# untitled.net
KiCad netlist of a schematic drawn in EAGLE
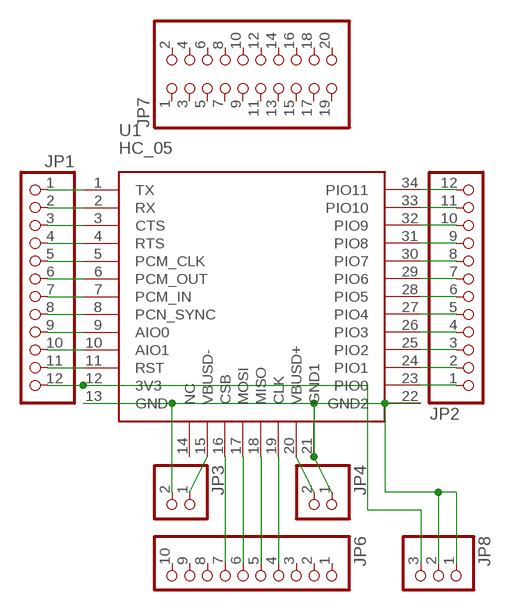
[diagram p0: schematic, sheet 1]

(export (version "E")
  (design (tool "Eeschema 10.0.6"))
  (components
    (comp (ref "JP1")
      (value "PINHD-1X12")
      (footprint "eagle-import:1X12")
      (libsource (lib "eagle-import") (part "PINHD-1X12"))
    )
    (comp (ref "JP2")
      (value "PINHD-1X12")
      (footprint "eagle-import:1X12")
      (libsource (lib "eagle-import") (part "PINHD-1X12"))
    )
    (comp (ref "JP3")
      (value "PINHD-1X2")
      (footprint "eagle-import:1X02")
      (libsource (lib "eagle-import") (part "PINHD-1X2"))
    )
    (comp (ref "JP4")
      (value "PINHD-1X2")
      (footprint "eagle-import:1X02")
      (libsource (lib "eagle-import") (part "PINHD-1X2"))
    )
    (comp (ref "JP6")
      (value "PINHD-1X10")
      (footprint "eagle-import:1X10")
      (libsource (lib "eagle-import") (part "PINHD-1X10"))
    )
    (comp (ref "JP7")
      (value "PINHD-2X10")
      (footprint "eagle-import:2X10")
      (libsource (lib "eagle-import") (part "PINHD-2X10"))
    )
    (comp (ref "JP8")
      (value "PINHD-1X3")
      (footprint "eagle-import:1X03")
      (libsource (lib "eagle-import") (part "PINHD-1X3"))
    )
    (comp (ref "U1")
      (value "HC_05")
      (footprint "eagle-import:BLUETOOTH_SMD")
      (libsource (lib "eagle-import") (part "HC_05"))
    )
  )
  (nets
    (net (code "1") (name "Net-(U1-3V3)") (class "Default")
      (node (ref "JP1") (pin "12") (pinfunction "12_12") (pintype "passive"))
      (node (ref "JP8") (pin "3") (pinfunction "3_3") (pintype "passive"))
      (node (ref "U1") (pin "12") (pinfunction "3V3_12") (pintype "bidirectional"))
    )
    (net (code "2") (name "Net-(U1-AIO0)") (class "Default")
      (node (ref "JP1") (pin "9") (pinfunction "9_9") (pintype "passive"))
      (node (ref "U1") (pin "9") (pinfunction "AIO0_9") (pintype "bidirectional"))
    )
    (net (code "3") (name "Net-(U1-AIO1)") (class "Default")
      (node (ref "JP1") (pin "10") (pinfunction "10_10") (pintype "passive"))
      (node (ref "U1") (pin "10") (pinfunction "AIO1_10") (pintype "bidirectional"))
    )
    (net (code "4") (name "Net-(U1-CLK)") (class "Default")
      (node (ref "JP6") (pin "4") (pinfunction "4_4") (pintype "passive"))
      (node (ref "U1") (pin "19") (pinfunction "CLK_19") (pintype "bidirectional"))
    )
    (net (code "5") (name "Net-(U1-CSB)") (class "Default")
      (node (ref "JP6") (pin "7") (pinfunction "7_7") (pintype "passive"))
      (node (ref "U1") (pin "16") (pinfunction "CSB_16") (pintype "bidirectional"))
    )
    (net (code "6") (name "Net-(U1-CTS)") (class "Default")
      (node (ref "JP1") (pin "3") (pinfunction "3_3") (pintype "passive"))
      (node (ref "U1") (pin "3") (pinfunction "CTS_3") (pintype "bidirectional"))
    )
    (net (code "7") (name "Net-(U1-GND)") (class "Default")
      (node (ref "JP3") (pin "2") (pinfunction "2_2") (pintype "passive"))
      (node (ref "JP4") (pin "1") (pinfunction "1_1") (pintype "passive"))
      (node (ref "JP8") (pin "1") (pinfunction "1_1") (pintype "passive"))
      (node (ref "JP8") (pin "2") (pinfunction "2_2") (pintype "passive"))
      (node (ref "U1") (pin "13") (pinfunction "GND_13") (pintype "bidirectional"))
      (node (ref "U1") (pin "21") (pinfunction "GND1_21") (pintype "bidirectional"))
      (node (ref "U1") (pin "22") (pinfunction "GND2_22") (pintype "bidirectional"))
    )
    (net (code "8") (name "Net-(U1-MISO)") (class "Default")
      (node (ref "JP6") (pin "5") (pinfunction "5_5") (pintype "passive"))
      (node (ref "U1") (pin "18") (pinfunction "MISO_18") (pintype "bidirectional"))
    )
    (net (code "9") (name "Net-(U1-MOSI)") (class "Default")
      (node (ref "JP6") (pin "6") (pinfunction "6_6") (pintype "passive"))
      (node (ref "U1") (pin "17") (pinfunction "MOSI_17") (pintype "bidirectional"))
    )
    (net (code "10") (name "Net-(U1-PCM_CLK)") (class "Default")
      (node (ref "JP1") (pin "5") (pinfunction "5_5") (pintype "passive"))
      (node (ref "U1") (pin "5") (pinfunction "PCM_CLK_5") (pintype "bidirectional"))
    )
    (net (code "11") (name "Net-(U1-PCM_IN)") (class "Default")
      (node (ref "JP1") (pin "7") (pinfunction "7_7") (pintype "passive"))
      (node (ref "U1") (pin "7") (pinfunction "PCM_IN_7") (pintype "bidirectional"))
    )
    (net (code "12") (name "Net-(U1-PCM_OUT)") (class "Default")
      (node (ref "JP1") (pin "6") (pinfunction "6_6") (pintype "passive"))
      (node (ref "U1") (pin "6") (pinfunction "PCM_OUT_6") (pintype "bidirectional"))
    )
    (net (code "13") (name "Net-(U1-PCN_SYNC)") (class "Default")
      (node (ref "JP1") (pin "8") (pinfunction "8_8") (pintype "passive"))
      (node (ref "U1") (pin "8") (pinfunction "PCN_SYNC_8") (pintype "bidirectional"))
    )
    (net (code "14") (name "Net-(U1-PIO0)") (class "Default")
      (node (ref "JP2") (pin "1") (pinfunction "1_1") (pintype "passive"))
      (node (ref "U1") (pin "23") (pinfunction "PIO0_23") (pintype "bidirectional"))
    )
    (net (code "15") (name "Net-(U1-PIO1)") (class "Default")
      (node (ref "JP2") (pin "2") (pinfunction "2_2") (pintype "passive"))
      (node (ref "U1") (pin "24") (pinfunction "PIO1_24") (pintype "bidirectional"))
    )
    (net (code "16") (name "Net-(U1-PIO2)") (class "Default")
      (node (ref "JP2") (pin "3") (pinfunction "3_3") (pintype "passive"))
      (node (ref "U1") (pin "25") (pinfunction "PIO2_25") (pintype "bidirectional"))
    )
    (net (code "17") (name "Net-(U1-PIO3)") (class "Default")
      (node (ref "JP2") (pin "4") (pinfunction "4_4") (pintype "passive"))
      (node (ref "U1") (pin "26") (pinfunction "PIO3_26") (pintype "bidirectional"))
    )
    (net (code "18") (name "Net-(U1-PIO4)") (class "Default")
      (node (ref "JP2") (pin "5") (pinfunction "5_5") (pintype "passive"))
      (node (ref "U1") (pin "27") (pinfunction "PIO4_27") (pintype "bidirectional"))
    )
    (net (code "19") (name "Net-(U1-PIO5)") (class "Default")
      (node (ref "JP2") (pin "6") (pinfunction "6_6") (pintype "passive"))
      (node (ref "U1") (pin "28") (pinfunction "PIO5_28") (pintype "bidirectional"))
    )
    (net (code "20") (name "Net-(U1-PIO6)") (class "Default")
      (node (ref "JP2") (pin "7") (pinfunction "7_7") (pintype "passive"))
      (node (ref "U1") (pin "29") (pinfunction "PIO6_29") (pintype "bidirectional"))
    )
    (net (code "21") (name "Net-(U1-PIO7)") (class "Default")
      (node (ref "JP2") (pin "8") (pinfunction "8_8") (pintype "passive"))
      (node (ref "U1") (pin "30") (pinfunction "PIO7_30") (pintype "bidirectional"))
    )
    (net (code "22") (name "Net-(U1-PIO8)") (class "Default")
      (node (ref "JP2") (pin "9") (pinfunction "9_9") (pintype "passive"))
      (node (ref "U1") (pin "31") (pinfunction "PIO8_31") (pintype "bidirectional"))
    )
    (net (code "23") (name "Net-(U1-PIO9)") (class "Default")
      (node (ref "JP2") (pin "10") (pinfunction "10_10") (pintype "passive"))
      (node (ref "U1") (pin "32") (pinfunction "PIO9_32") (pintype "bidirectional"))
    )
    (net (code "24") (name "Net-(U1-PIO10)") (class "Default")
      (node (ref "JP2") (pin "11") (pinfunction "11_11") (pintype "passive"))
      (node (ref "U1") (pin "33") (pinfunction "PIO10_33") (pintype "bidirectional"))
    )
    (net (code "25") (name "Net-(U1-PIO11)") (class "Default")
      (node (ref "JP2") (pin "12") (pinfunction "12_12") (pintype "passive"))
      (node (ref "U1") (pin "34") (pinfunction "PIO11_34") (pintype "bidirectional"))
    )
    (net (code "26") (name "Net-(U1-RST)") (class "Default")
      (node (ref "JP1") (pin "11") (pinfunction "11_11") (pintype "passive"))
      (node (ref "U1") (pin "11") (pinfunction "RST_11") (pintype "bidirectional"))
    )
    (net (code "27") (name "Net-(U1-RTS)") (class "Default")
      (node (ref "JP1") (pin "4") (pinfunction "4_4") (pintype "passive"))
      (node (ref "U1") (pin "4") (pinfunction "RTS_4") (pintype "bidirectional"))
    )
    (net (code "28") (name "Net-(U1-RX)") (class "Default")
      (node (ref "JP1") (pin "2") (pinfunction "2_2") (pintype "passive"))
      (node (ref "U1") (pin "2") (pinfunction "RX_2") (pintype "bidirectional"))
    )
    (net (code "29") (name "Net-(U1-TX)") (class "Default")
      (node (ref "JP1") (pin "1") (pinfunction "1_1") (pintype "passive"))
      (node (ref "U1") (pin "1") (pinfunction "TX_1") (pintype "bidirectional"))
    )
    (net (code "30") (name "Net-(U1-VBUSD+)") (class "Default")
      (node (ref "JP4") (pin "2") (pinfunction "2_2") (pintype "passive"))
      (node (ref "U1") (pin "20") (pinfunction "VBUSD+_20") (pintype "bidirectional"))
    )
    (net (code "31") (name "Net-(U1-VBUSD-)") (class "Default")
      (node (ref "JP3") (pin "1") (pinfunction "1_1") (pintype "passive"))
      (node (ref "U1") (pin "15") (pinfunction "VBUSD-_15") (pintype "bidirectional"))
    )
    (net (code "32") (name "unconnected-(JP6-Pad1)") (class "Default")
      (node (ref "JP6") (pin "1") (pinfunction "1_1") (pintype "passive"))
    )
    (net (code "33") (name "unconnected-(JP6-Pad2)") (class "Default")
      (node (ref "JP6") (pin "2") (pinfunction "2_2") (pintype "passive"))
    )
    (net (code "34") (name "unconnected-(JP6-Pad3)") (class "Default")
      (node (ref "JP6") (pin "3") (pinfunction "3_3") (pintype "passive"))
    )
    (net (code "35") (name "unconnected-(JP6-Pad8)") (class "Default")
      (node (ref "JP6") (pin "8") (pinfunction "8_8") (pintype "passive"))
    )
    (net (code "36") (name "unconnected-(JP6-Pad9)") (class "Default")
      (node (ref "JP6") (pin "9") (pinfunction "9_9") (pintype "passive"))
    )
    (net (code "37") (name "unconnected-(JP6-Pad10)") (class "Default")
      (node (ref "JP6") (pin "10") (pinfunction "10_10") (pintype "passive"))
    )
    (net (code "38") (name "unconnected-(JP7-Pad1)") (class "Default")
      (node (ref "JP7") (pin "1") (pinfunction "1_1") (pintype "passive"))
    )
    (net (code "39") (name "unconnected-(JP7-Pad2)") (class "Default")
      (node (ref "JP7") (pin "2") (pinfunction "2_2") (pintype "passive"))
    )
    (net (code "40") (name "unconnected-(JP7-Pad3)") (class "Default")
      (node (ref "JP7") (pin "3") (pinfunction "3_3") (pintype "passive"))
    )
    (net (code "41") (name "unconnected-(JP7-Pad4)") (class "Default")
      (node (ref "JP7") (pin "4") (pinfunction "4_4") (pintype "passive"))
    )
    (net (code "42") (name "unconnected-(JP7-Pad5)") (class "Default")
      (node (ref "JP7") (pin "5") (pinfunction "5_5") (pintype "passive"))
    )
    (net (code "43") (name "unconnected-(JP7-Pad6)") (class "Default")
      (node (ref "JP7") (pin "6") (pinfunction "6_6") (pintype "passive"))
    )
    (net (code "44") (name "unconnected-(JP7-Pad7)") (class "Default")
      (node (ref "JP7") (pin "7") (pinfunction "7_7") (pintype "passive"))
    )
    (net (code "45") (name "unconnected-(JP7-Pad8)") (class "Default")
      (node (ref "JP7") (pin "8") (pinfunction "8_8") (pintype "passive"))
    )
    (net (code "46") (name "unconnected-(JP7-Pad9)") (class "Default")
      (node (ref "JP7") (pin "9") (pinfunction "9_9") (pintype "passive"))
    )
    (net (code "47") (name "unconnected-(JP7-Pad10)") (class "Default")
      (node (ref "JP7") (pin "10") (pinfunction "10_10") (pintype "passive"))
    )
    (net (code "48") (name "unconnected-(JP7-Pad11)") (class "Default")
      (node (ref "JP7") (pin "11") (pinfunction "11_11") (pintype "passive"))
    )
    (net (code "49") (name "unconnected-(JP7-Pad12)") (class "Default")
      (node (ref "JP7") (pin "12") (pinfunction "12_12") (pintype "passive"))
    )
    (net (code "50") (name "unconnected-(JP7-Pad13)") (class "Default")
      (node (ref "JP7") (pin "13") (pinfunction "13_13") (pintype "passive"))
    )
    (net (code "51") (name "unconnected-(JP7-Pad14)") (class "Default")
      (node (ref "JP7") (pin "14") (pinfunction "14_14") (pintype "passive"))
    )
    (net (code "52") (name "unconnected-(JP7-Pad15)") (class "Default")
      (node (ref "JP7") (pin "15") (pinfunction "15_15") (pintype "passive"))
    )
    (net (code "53") (name "unconnected-(JP7-Pad16)") (class "Default")
      (node (ref "JP7") (pin "16") (pinfunction "16_16") (pintype "passive"))
    )
    (net (code "54") (name "unconnected-(JP7-Pad17)") (class "Default")
      (node (ref "JP7") (pin "17") (pinfunction "17_17") (pintype "passive"))
    )
    (net (code "55") (name "unconnected-(JP7-Pad18)") (class "Default")
      (node (ref "JP7") (pin "18") (pinfunction "18_18") (pintype "passive"))
    )
    (net (code "56") (name "unconnected-(JP7-Pad19)") (class "Default")
      (node (ref "JP7") (pin "19") (pinfunction "19_19") (pintype "passive"))
    )
    (net (code "57") (name "unconnected-(JP7-Pad20)") (class "Default")
      (node (ref "JP7") (pin "20") (pinfunction "20_20") (pintype "passive"))
    )
    (net (code "58") (name "unconnected-(U1-NC-Pad14)") (class "Default")
      (node (ref "U1") (pin "14") (pinfunction "NC_14") (pintype "bidirectional"))
    )
  )
)
